# FlyballETS-Board.net
KiCad netlist of a schematic drawn in EAGLE
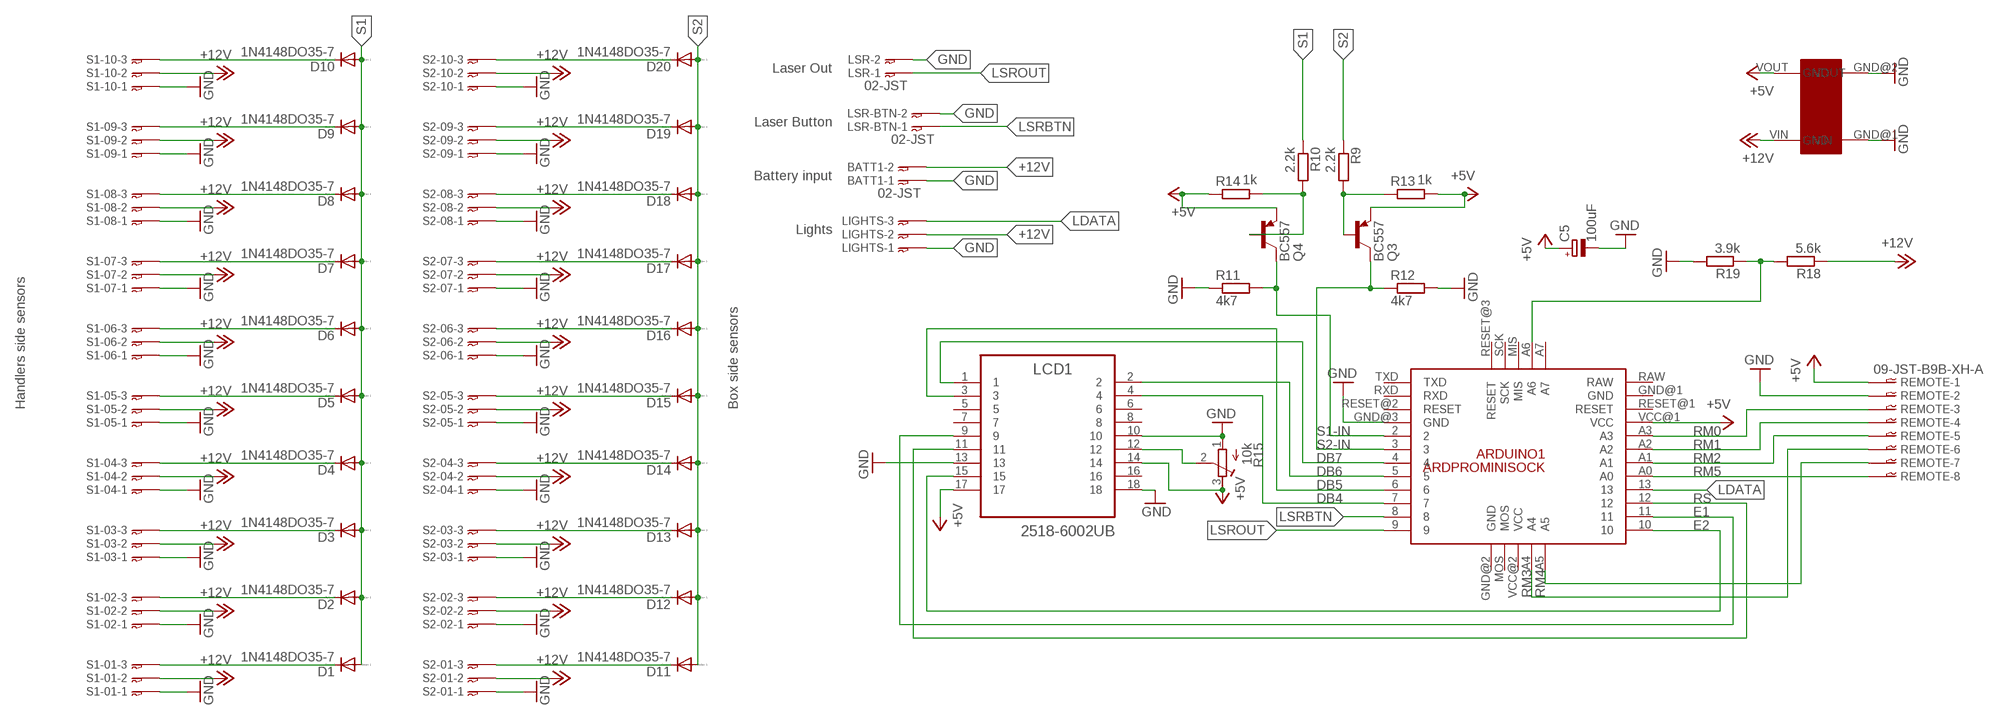
[diagram p0: schematic, sheet 1]

(export (version "E")
  (design (tool "Eeschema 10.0.6"))
  (components
    (comp (ref "ARDUINO1")
      (value "ARDPROMINISOCK")
      (footprint "eagle-import:ARDPROMINISOCK")
      (libsource (lib "eagle-import") (part "ARDPROMINISOCK"))
    )
    (comp (ref "BATT1")
      (value "02-JST")
      (footprint "eagle-import:B2B-XH")
      (libsource (lib "eagle-import") (part "02-JST"))
    )
    (comp (ref "C5")
      (value "100uF")
      (footprint "eagle-import:E2,5-6E")
      (libsource (lib "eagle-import") (part "CPOL-EUE2,5-6E"))
    )
    (comp (ref "D1")
      (value "1N4148DO35-7")
      (footprint "eagle-import:DO35-7")
      (libsource (lib "eagle-import") (part "1N4148DO35-7"))
    )
    (comp (ref "D2")
      (value "1N4148DO35-7")
      (footprint "eagle-import:DO35-7")
      (libsource (lib "eagle-import") (part "1N4148DO35-7"))
    )
    (comp (ref "D3")
      (value "1N4148DO35-7")
      (footprint "eagle-import:DO35-7")
      (libsource (lib "eagle-import") (part "1N4148DO35-7"))
    )
    (comp (ref "D4")
      (value "1N4148DO35-7")
      (footprint "eagle-import:DO35-7")
      (libsource (lib "eagle-import") (part "1N4148DO35-7"))
    )
    (comp (ref "D5")
      (value "1N4148DO35-7")
      (footprint "eagle-import:DO35-7")
      (libsource (lib "eagle-import") (part "1N4148DO35-7"))
    )
    (comp (ref "D6")
      (value "1N4148DO35-7")
      (footprint "eagle-import:DO35-7")
      (libsource (lib "eagle-import") (part "1N4148DO35-7"))
    )
    (comp (ref "D7")
      (value "1N4148DO35-7")
      (footprint "eagle-import:DO35-7")
      (libsource (lib "eagle-import") (part "1N4148DO35-7"))
    )
    (comp (ref "D8")
      (value "1N4148DO35-7")
      (footprint "eagle-import:DO35-7")
      (libsource (lib "eagle-import") (part "1N4148DO35-7"))
    )
    (comp (ref "D9")
      (value "1N4148DO35-7")
      (footprint "eagle-import:DO35-7")
      (libsource (lib "eagle-import") (part "1N4148DO35-7"))
    )
    (comp (ref "D10")
      (value "1N4148DO35-7")
      (footprint "eagle-import:DO35-7")
      (libsource (lib "eagle-import") (part "1N4148DO35-7"))
    )
    (comp (ref "D11")
      (value "1N4148DO35-7")
      (footprint "eagle-import:DO35-7")
      (libsource (lib "eagle-import") (part "1N4148DO35-7"))
    )
    (comp (ref "D12")
      (value "1N4148DO35-7")
      (footprint "eagle-import:DO35-7")
      (libsource (lib "eagle-import") (part "1N4148DO35-7"))
    )
    (comp (ref "D13")
      (value "1N4148DO35-7")
      (footprint "eagle-import:DO35-7")
      (libsource (lib "eagle-import") (part "1N4148DO35-7"))
    )
    (comp (ref "D14")
      (value "1N4148DO35-7")
      (footprint "eagle-import:DO35-7")
      (libsource (lib "eagle-import") (part "1N4148DO35-7"))
    )
    (comp (ref "D15")
      (value "1N4148DO35-7")
      (footprint "eagle-import:DO35-7")
      (libsource (lib "eagle-import") (part "1N4148DO35-7"))
    )
    (comp (ref "D16")
      (value "1N4148DO35-7")
      (footprint "eagle-import:DO35-7")
      (libsource (lib "eagle-import") (part "1N4148DO35-7"))
    )
    (comp (ref "D17")
      (value "1N4148DO35-7")
      (footprint "eagle-import:DO35-7")
      (libsource (lib "eagle-import") (part "1N4148DO35-7"))
    )
    (comp (ref "D18")
      (value "1N4148DO35-7")
      (footprint "eagle-import:DO35-7")
      (libsource (lib "eagle-import") (part "1N4148DO35-7"))
    )
    (comp (ref "D19")
      (value "1N4148DO35-7")
      (footprint "eagle-import:DO35-7")
      (libsource (lib "eagle-import") (part "1N4148DO35-7"))
    )
    (comp (ref "D20")
      (value "1N4148DO35-7")
      (footprint "eagle-import:DO35-7")
      (libsource (lib "eagle-import") (part "1N4148DO35-7"))
    )
    (comp (ref "LCD1")
      (value "2518-6002UB")
      (footprint "eagle-import:3M_2518-6002UB")
      (libsource (lib "eagle-import") (part "2518-6002UB"))
    )
    (comp (ref "LIGHTS")
      (value "03-JST-B3B-XH-A")
      (footprint "eagle-import:B3B-XH")
      (libsource (lib "eagle-import") (part "03-JST-B3B-XH-A"))
    )
    (comp (ref "LSR")
      (value "02-JST")
      (footprint "eagle-import:B2B-XH")
      (libsource (lib "eagle-import") (part "02-JST"))
    )
    (comp (ref "LSR-BTN")
      (value "02-JST")
      (footprint "eagle-import:B2B-XH")
      (libsource (lib "eagle-import") (part "02-JST"))
    )
    (comp (ref "Q3")
      (value "BC557")
      (footprint "eagle-import:TO92")
      (libsource (lib "eagle-import") (part "BC557"))
    )
    (comp (ref "Q4")
      (value "BC557")
      (footprint "eagle-import:TO92")
      (libsource (lib "eagle-import") (part "BC557"))
    )
    (comp (ref "R9")
      (value "2.2k")
      (footprint "eagle-import:0207_10")
      (libsource (lib "eagle-import") (part "R-EU_0207/10"))
    )
    (comp (ref "R10")
      (value "2.2k")
      (footprint "eagle-import:0207_10")
      (libsource (lib "eagle-import") (part "R-EU_0207/10"))
    )
    (comp (ref "R11")
      (value "4k7")
      (footprint "eagle-import:0207_10")
      (libsource (lib "eagle-import") (part "R-EU_0207/10"))
    )
    (comp (ref "R12")
      (value "4k7")
      (footprint "eagle-import:0207_10")
      (libsource (lib "eagle-import") (part "R-EU_0207/10"))
    )
    (comp (ref "R13")
      (value "1k")
      (footprint "eagle-import:0207_10")
      (libsource (lib "eagle-import") (part "R-EU_0207/10"))
    )
    (comp (ref "R14")
      (value "1k")
      (footprint "eagle-import:0207_10")
      (libsource (lib "eagle-import") (part "R-EU_0207/10"))
    )
    (comp (ref "R15")
      (value "10k")
      (footprint "eagle-import:RTRIM3339P")
      (libsource (lib "eagle-import") (part "R-TRIMM3339P"))
    )
    (comp (ref "R18")
      (value "5.6k")
      (footprint "eagle-import:0207_10")
      (libsource (lib "eagle-import") (part "resistor_348_R-EU_0207/10"))
    )
    (comp (ref "R19")
      (value "3.9k")
      (footprint "eagle-import:0207_10")
      (libsource (lib "eagle-import") (part "resistor_348_R-EU_0207/10"))
    )
    (comp (ref "REMOTE")
      (value "09-JST-B9B-XH-A")
      (footprint "eagle-import:B9B-XH")
      (libsource (lib "eagle-import") (part "09-JST-B9B-XH-A"))
    )
    (comp (ref "S1-01")
      (value "03-JST-B3B-XH-A")
      (footprint "eagle-import:B3B-XH")
      (libsource (lib "eagle-import") (part "03-JST-B3B-XH-A"))
    )
    (comp (ref "S1-02")
      (value "03-JST-B3B-XH-A")
      (footprint "eagle-import:B3B-XH")
      (libsource (lib "eagle-import") (part "03-JST-B3B-XH-A"))
    )
    (comp (ref "S1-03")
      (value "03-JST-B3B-XH-A")
      (footprint "eagle-import:B3B-XH")
      (libsource (lib "eagle-import") (part "03-JST-B3B-XH-A"))
    )
    (comp (ref "S1-04")
      (value "03-JST-B3B-XH-A")
      (footprint "eagle-import:B3B-XH")
      (libsource (lib "eagle-import") (part "03-JST-B3B-XH-A"))
    )
    (comp (ref "S1-05")
      (value "03-JST-B3B-XH-A")
      (footprint "eagle-import:B3B-XH")
      (libsource (lib "eagle-import") (part "03-JST-B3B-XH-A"))
    )
    (comp (ref "S1-06")
      (value "03-JST-B3B-XH-A")
      (footprint "eagle-import:B3B-XH")
      (libsource (lib "eagle-import") (part "03-JST-B3B-XH-A"))
    )
    (comp (ref "S1-07")
      (value "03-JST-B3B-XH-A")
      (footprint "eagle-import:B3B-XH")
      (libsource (lib "eagle-import") (part "03-JST-B3B-XH-A"))
    )
    (comp (ref "S1-08")
      (value "03-JST-B3B-XH-A")
      (footprint "eagle-import:B3B-XH")
      (libsource (lib "eagle-import") (part "03-JST-B3B-XH-A"))
    )
    (comp (ref "S1-09")
      (value "03-JST-B3B-XH-A")
      (footprint "eagle-import:B3B-XH")
      (libsource (lib "eagle-import") (part "03-JST-B3B-XH-A"))
    )
    (comp (ref "S1-10")
      (value "03-JST-B3B-XH-A")
      (footprint "eagle-import:B3B-XH")
      (libsource (lib "eagle-import") (part "03-JST-B3B-XH-A"))
    )
    (comp (ref "S2-01")
      (value "03-JST-B3B-XH-A")
      (footprint "eagle-import:B3B-XH")
      (libsource (lib "eagle-import") (part "03-JST-B3B-XH-A"))
    )
    (comp (ref "S2-02")
      (value "03-JST-B3B-XH-A")
      (footprint "eagle-import:B3B-XH")
      (libsource (lib "eagle-import") (part "03-JST-B3B-XH-A"))
    )
    (comp (ref "S2-03")
      (value "03-JST-B3B-XH-A")
      (footprint "eagle-import:B3B-XH")
      (libsource (lib "eagle-import") (part "03-JST-B3B-XH-A"))
    )
    (comp (ref "S2-04")
      (value "03-JST-B3B-XH-A")
      (footprint "eagle-import:B3B-XH")
      (libsource (lib "eagle-import") (part "03-JST-B3B-XH-A"))
    )
    (comp (ref "S2-05")
      (value "03-JST-B3B-XH-A")
      (footprint "eagle-import:B3B-XH")
      (libsource (lib "eagle-import") (part "03-JST-B3B-XH-A"))
    )
    (comp (ref "S2-06")
      (value "03-JST-B3B-XH-A")
      (footprint "eagle-import:B3B-XH")
      (libsource (lib "eagle-import") (part "03-JST-B3B-XH-A"))
    )
    (comp (ref "S2-07")
      (value "03-JST-B3B-XH-A")
      (footprint "eagle-import:B3B-XH")
      (libsource (lib "eagle-import") (part "03-JST-B3B-XH-A"))
    )
    (comp (ref "S2-08")
      (value "03-JST-B3B-XH-A")
      (footprint "eagle-import:B3B-XH")
      (libsource (lib "eagle-import") (part "03-JST-B3B-XH-A"))
    )
    (comp (ref "S2-09")
      (value "03-JST-B3B-XH-A")
      (footprint "eagle-import:B3B-XH")
      (libsource (lib "eagle-import") (part "03-JST-B3B-XH-A"))
    )
    (comp (ref "S2-10")
      (value "03-JST-B3B-XH-A")
      (footprint "eagle-import:B3B-XH")
      (libsource (lib "eagle-import") (part "03-JST-B3B-XH-A"))
    )
    (comp (ref "U$2")
      (value "LM2596-BOARD")
      (footprint "eagle-import:LM2596-BOARD")
      (libsource (lib "eagle-import") (part "LM2596-BOARD"))
    )
  )
  (nets
    (net (code "1") (name "+5V") (class "Default")
      (node (ref "ARDUINO1") (pin "VCC@1") (pinfunction "VCC_VCC@1") (pintype "bidirectional"))
      (node (ref "C5") (pin "+") (pinfunction "+_+") (pintype "passive"))
      (node (ref "LCD1") (pin "14") (pinfunction "14_14") (pintype "passive"))
      (node (ref "LCD1") (pin "17") (pinfunction "17_17") (pintype "passive"))
      (node (ref "Q3") (pin "1") (pinfunction "E_1") (pintype "passive"))
      (node (ref "Q4") (pin "1") (pinfunction "E_1") (pintype "passive"))
      (node (ref "R13") (pin "2") (pinfunction "2_2") (pintype "passive"))
      (node (ref "R14") (pin "1") (pinfunction "1_1") (pintype "passive"))
      (node (ref "R15") (pin "3") (pinfunction "E_3") (pintype "passive"))
      (node (ref "REMOTE") (pin "P$1") (pinfunction "1_P$1") (pintype "passive"))
      (node (ref "U$2") (pin "VOUT") (pinfunction "VOUT_VOUT") (pintype "bidirectional"))
    )
    (net (code "2") (name "+12V") (class "Default")
      (node (ref "BATT1") (pin "P$2") (pinfunction "1_P$2") (pintype "passive"))
      (node (ref "LIGHTS") (pin "P$2") (pinfunction "1_P$2") (pintype "passive"))
      (node (ref "R18") (pin "1") (pinfunction "1_1") (pintype "passive"))
      (node (ref "S1-01") (pin "P$2") (pinfunction "1_P$2") (pintype "passive"))
      (node (ref "S1-02") (pin "P$2") (pinfunction "1_P$2") (pintype "passive"))
      (node (ref "S1-03") (pin "P$2") (pinfunction "1_P$2") (pintype "passive"))
      (node (ref "S1-04") (pin "P$2") (pinfunction "1_P$2") (pintype "passive"))
      (node (ref "S1-05") (pin "P$2") (pinfunction "1_P$2") (pintype "passive"))
      (node (ref "S1-06") (pin "P$2") (pinfunction "1_P$2") (pintype "passive"))
      (node (ref "S1-07") (pin "P$2") (pinfunction "1_P$2") (pintype "passive"))
      (node (ref "S1-08") (pin "P$2") (pinfunction "1_P$2") (pintype "passive"))
      (node (ref "S1-09") (pin "P$2") (pinfunction "1_P$2") (pintype "passive"))
      (node (ref "S1-10") (pin "P$2") (pinfunction "1_P$2") (pintype "passive"))
      (node (ref "S2-01") (pin "P$2") (pinfunction "1_P$2") (pintype "passive"))
      (node (ref "S2-02") (pin "P$2") (pinfunction "1_P$2") (pintype "passive"))
      (node (ref "S2-03") (pin "P$2") (pinfunction "1_P$2") (pintype "passive"))
      (node (ref "S2-04") (pin "P$2") (pinfunction "1_P$2") (pintype "passive"))
      (node (ref "S2-05") (pin "P$2") (pinfunction "1_P$2") (pintype "passive"))
      (node (ref "S2-06") (pin "P$2") (pinfunction "1_P$2") (pintype "passive"))
      (node (ref "S2-07") (pin "P$2") (pinfunction "1_P$2") (pintype "passive"))
      (node (ref "S2-08") (pin "P$2") (pinfunction "1_P$2") (pintype "passive"))
      (node (ref "S2-09") (pin "P$2") (pinfunction "1_P$2") (pintype "passive"))
      (node (ref "S2-10") (pin "P$2") (pinfunction "1_P$2") (pintype "passive"))
      (node (ref "U$2") (pin "VIN") (pinfunction "VIN_VIN") (pintype "bidirectional"))
    )
    (net (code "3") (name "/DB4") (class "Default")
      (node (ref "ARDUINO1") (pin "7") (pinfunction "7_7") (pintype "bidirectional"))
      (node (ref "LCD1") (pin "4") (pinfunction "4_4") (pintype "passive"))
    )
    (net (code "4") (name "/DB5") (class "Default")
      (node (ref "ARDUINO1") (pin "6") (pinfunction "6_6") (pintype "bidirectional"))
      (node (ref "LCD1") (pin "3") (pinfunction "3_3") (pintype "passive"))
    )
    (net (code "5") (name "/DB6") (class "Default")
      (node (ref "ARDUINO1") (pin "5") (pinfunction "5_5") (pintype "bidirectional"))
      (node (ref "LCD1") (pin "2") (pinfunction "2_2") (pintype "passive"))
    )
    (net (code "6") (name "/DB7") (class "Default")
      (node (ref "ARDUINO1") (pin "4") (pinfunction "4_4") (pintype "bidirectional"))
      (node (ref "LCD1") (pin "1") (pinfunction "1_1") (pintype "passive"))
    )
    (net (code "7") (name "/E1") (class "Default")
      (node (ref "ARDUINO1") (pin "11") (pinfunction "11_11") (pintype "bidirectional"))
      (node (ref "LCD1") (pin "9") (pinfunction "9_9") (pintype "passive"))
    )
    (net (code "8") (name "/E2") (class "Default")
      (node (ref "ARDUINO1") (pin "10") (pinfunction "10_10") (pintype "bidirectional"))
      (node (ref "LCD1") (pin "15") (pinfunction "15_15") (pintype "passive"))
    )
    (net (code "9") (name "/RM0") (class "Default")
      (node (ref "ARDUINO1") (pin "A3") (pinfunction "A3_A3") (pintype "bidirectional"))
      (node (ref "REMOTE") (pin "P$3") (pinfunction "1_P$3") (pintype "passive"))
    )
    (net (code "10") (name "/RM1") (class "Default")
      (node (ref "ARDUINO1") (pin "A2") (pinfunction "A2_A2") (pintype "bidirectional"))
      (node (ref "REMOTE") (pin "P$4") (pinfunction "1_P$4") (pintype "passive"))
    )
    (net (code "11") (name "/RM2") (class "Default")
      (node (ref "ARDUINO1") (pin "A1") (pinfunction "A1_A1") (pintype "bidirectional"))
      (node (ref "REMOTE") (pin "P$5") (pinfunction "1_P$5") (pintype "passive"))
    )
    (net (code "12") (name "/RM3") (class "Default")
      (node (ref "ARDUINO1") (pin "A4") (pinfunction "A4_A4") (pintype "bidirectional"))
      (node (ref "REMOTE") (pin "P$6") (pinfunction "1_P$6") (pintype "passive"))
    )
    (net (code "13") (name "/RM4") (class "Default")
      (node (ref "ARDUINO1") (pin "A5") (pinfunction "A5_A5") (pintype "bidirectional"))
      (node (ref "REMOTE") (pin "P$7") (pinfunction "1_P$7") (pintype "passive"))
    )
    (net (code "14") (name "/RM5") (class "Default")
      (node (ref "ARDUINO1") (pin "A0") (pinfunction "A0_A0") (pintype "bidirectional"))
      (node (ref "REMOTE") (pin "P$8") (pinfunction "1_P$8") (pintype "passive"))
    )
    (net (code "15") (name "/RS") (class "Default")
      (node (ref "ARDUINO1") (pin "12") (pinfunction "12_12") (pintype "bidirectional"))
      (node (ref "LCD1") (pin "11") (pinfunction "11_11") (pintype "passive"))
    )
    (net (code "16") (name "/S1-IN") (class "Default")
      (node (ref "ARDUINO1") (pin "2") (pinfunction "2_2") (pintype "bidirectional"))
      (node (ref "Q4") (pin "3") (pinfunction "C_3") (pintype "passive"))
      (node (ref "R11") (pin "2") (pinfunction "2_2") (pintype "passive"))
    )
    (net (code "17") (name "/S2-IN") (class "Default")
      (node (ref "ARDUINO1") (pin "3") (pinfunction "3_3") (pintype "bidirectional"))
      (node (ref "Q3") (pin "3") (pinfunction "C_3") (pintype "passive"))
      (node (ref "R12") (pin "1") (pinfunction "1_1") (pintype "passive"))
    )
    (net (code "18") (name "GND") (class "Default")
      (node (ref "ARDUINO1") (pin "GND@3") (pinfunction "GND_GND@3") (pintype "bidirectional"))
      (node (ref "BATT1") (pin "P$1") (pinfunction "1_P$1") (pintype "passive"))
      (node (ref "C5") (pin "-") (pinfunction "-_-") (pintype "passive"))
      (node (ref "LCD1") (pin "10") (pinfunction "10_10") (pintype "passive"))
      (node (ref "LCD1") (pin "13") (pinfunction "13_13") (pintype "passive"))
      (node (ref "LCD1") (pin "18") (pinfunction "18_18") (pintype "passive"))
      (node (ref "LIGHTS") (pin "P$1") (pinfunction "1_P$1") (pintype "passive"))
      (node (ref "LSR") (pin "P$2") (pinfunction "1_P$2") (pintype "passive"))
      (node (ref "LSR-BTN") (pin "P$2") (pinfunction "1_P$2") (pintype "passive"))
      (node (ref "R11") (pin "1") (pinfunction "1_1") (pintype "passive"))
      (node (ref "R12") (pin "2") (pinfunction "2_2") (pintype "passive"))
      (node (ref "R15") (pin "1") (pinfunction "A_1") (pintype "passive"))
      (node (ref "R19") (pin "2") (pinfunction "2_2") (pintype "passive"))
      (node (ref "REMOTE") (pin "P$2") (pinfunction "1_P$2") (pintype "passive"))
      (node (ref "S1-01") (pin "P$1") (pinfunction "1_P$1") (pintype "passive"))
      (node (ref "S1-02") (pin "P$1") (pinfunction "1_P$1") (pintype "passive"))
      (node (ref "S1-03") (pin "P$1") (pinfunction "1_P$1") (pintype "passive"))
      (node (ref "S1-04") (pin "P$1") (pinfunction "1_P$1") (pintype "passive"))
      (node (ref "S1-05") (pin "P$1") (pinfunction "1_P$1") (pintype "passive"))
      (node (ref "S1-06") (pin "P$1") (pinfunction "1_P$1") (pintype "passive"))
      (node (ref "S1-07") (pin "P$1") (pinfunction "1_P$1") (pintype "passive"))
      (node (ref "S1-08") (pin "P$1") (pinfunction "1_P$1") (pintype "passive"))
      (node (ref "S1-09") (pin "P$1") (pinfunction "1_P$1") (pintype "passive"))
      (node (ref "S1-10") (pin "P$1") (pinfunction "1_P$1") (pintype "passive"))
      (node (ref "S2-01") (pin "P$1") (pinfunction "1_P$1") (pintype "passive"))
      (node (ref "S2-02") (pin "P$1") (pinfunction "1_P$1") (pintype "passive"))
      (node (ref "S2-03") (pin "P$1") (pinfunction "1_P$1") (pintype "passive"))
      (node (ref "S2-04") (pin "P$1") (pinfunction "1_P$1") (pintype "passive"))
      (node (ref "S2-05") (pin "P$1") (pinfunction "1_P$1") (pintype "passive"))
      (node (ref "S2-06") (pin "P$1") (pinfunction "1_P$1") (pintype "passive"))
      (node (ref "S2-07") (pin "P$1") (pinfunction "1_P$1") (pintype "passive"))
      (node (ref "S2-08") (pin "P$1") (pinfunction "1_P$1") (pintype "passive"))
      (node (ref "S2-09") (pin "P$1") (pinfunction "1_P$1") (pintype "passive"))
      (node (ref "S2-10") (pin "P$1") (pinfunction "1_P$1") (pintype "passive"))
      (node (ref "U$2") (pin "GND@1") (pinfunction "GND_GND@1") (pintype "bidirectional"))
      (node (ref "U$2") (pin "GND@2") (pinfunction "GND_GND@2") (pintype "bidirectional"))
    )
    (net (code "19") (name "LDATA") (class "Default")
      (node (ref "ARDUINO1") (pin "13") (pinfunction "13_13") (pintype "bidirectional"))
      (node (ref "LIGHTS") (pin "P$3") (pinfunction "1_P$3") (pintype "passive"))
    )
    (net (code "20") (name "LSRBTN") (class "Default")
      (node (ref "ARDUINO1") (pin "8") (pinfunction "8_8") (pintype "bidirectional"))
      (node (ref "LSR-BTN") (pin "P$1") (pinfunction "1_P$1") (pintype "passive"))
    )
    (net (code "21") (name "LSROUT") (class "Default")
      (node (ref "ARDUINO1") (pin "9") (pinfunction "9_9") (pintype "bidirectional"))
      (node (ref "LSR") (pin "P$1") (pinfunction "1_P$1") (pintype "passive"))
    )
    (net (code "22") (name "Net-(ARDUINO1-PadA6)") (class "Default")
      (node (ref "ARDUINO1") (pin "A6") (pinfunction "A6_A6") (pintype "bidirectional"))
      (node (ref "R18") (pin "2") (pinfunction "2_2") (pintype "passive"))
      (node (ref "R19") (pin "1") (pinfunction "1_1") (pintype "passive"))
    )
    (net (code "23") (name "Net-(Q3-B)") (class "Default")
      (node (ref "Q3") (pin "2") (pinfunction "B_2") (pintype "passive"))
      (node (ref "R13") (pin "1") (pinfunction "1_1") (pintype "passive"))
      (node (ref "R9") (pin "2") (pinfunction "2_2") (pintype "passive"))
    )
    (net (code "24") (name "Net-(Q4-B)") (class "Default")
      (node (ref "Q4") (pin "2") (pinfunction "B_2") (pintype "passive"))
      (node (ref "R10") (pin "2") (pinfunction "2_2") (pintype "passive"))
      (node (ref "R14") (pin "2") (pinfunction "2_2") (pintype "passive"))
    )
    (net (code "25") (name "Net-(R15-S)") (class "Default")
      (node (ref "LCD1") (pin "12") (pinfunction "12_12") (pintype "passive"))
      (node (ref "R15") (pin "2") (pinfunction "S_2") (pintype "passive"))
    )
    (net (code "26") (name "Net-(S1-01C-1)") (class "Default")
      (node (ref "D1") (pin "C") (pinfunction "C_C") (pintype "passive"))
      (node (ref "S1-01") (pin "P$3") (pinfunction "1_P$3") (pintype "passive"))
    )
    (net (code "27") (name "Net-(S1-02C-1)") (class "Default")
      (node (ref "D2") (pin "C") (pinfunction "C_C") (pintype "passive"))
      (node (ref "S1-02") (pin "P$3") (pinfunction "1_P$3") (pintype "passive"))
    )
    (net (code "28") (name "Net-(S1-03C-1)") (class "Default")
      (node (ref "D3") (pin "C") (pinfunction "C_C") (pintype "passive"))
      (node (ref "S1-03") (pin "P$3") (pinfunction "1_P$3") (pintype "passive"))
    )
    (net (code "29") (name "Net-(S1-04C-1)") (class "Default")
      (node (ref "D4") (pin "C") (pinfunction "C_C") (pintype "passive"))
      (node (ref "S1-04") (pin "P$3") (pinfunction "1_P$3") (pintype "passive"))
    )
    (net (code "30") (name "Net-(S1-05C-1)") (class "Default")
      (node (ref "D5") (pin "C") (pinfunction "C_C") (pintype "passive"))
      (node (ref "S1-05") (pin "P$3") (pinfunction "1_P$3") (pintype "passive"))
    )
    (net (code "31") (name "Net-(S1-06C-1)") (class "Default")
      (node (ref "D6") (pin "C") (pinfunction "C_C") (pintype "passive"))
      (node (ref "S1-06") (pin "P$3") (pinfunction "1_P$3") (pintype "passive"))
    )
    (net (code "32") (name "Net-(S1-07C-1)") (class "Default")
      (node (ref "D7") (pin "C") (pinfunction "C_C") (pintype "passive"))
      (node (ref "S1-07") (pin "P$3") (pinfunction "1_P$3") (pintype "passive"))
    )
    (net (code "33") (name "Net-(S1-08C-1)") (class "Default")
      (node (ref "D8") (pin "C") (pinfunction "C_C") (pintype "passive"))
      (node (ref "S1-08") (pin "P$3") (pinfunction "1_P$3") (pintype "passive"))
    )
    (net (code "34") (name "Net-(S1-09C-1)") (class "Default")
      (node (ref "D9") (pin "C") (pinfunction "C_C") (pintype "passive"))
      (node (ref "S1-09") (pin "P$3") (pinfunction "1_P$3") (pintype "passive"))
    )
    (net (code "35") (name "Net-(S1-10C-1)") (class "Default")
      (node (ref "D10") (pin "C") (pinfunction "C_C") (pintype "passive"))
      (node (ref "S1-10") (pin "P$3") (pinfunction "1_P$3") (pintype "passive"))
    )
    (net (code "36") (name "Net-(S2-01C-1)") (class "Default")
      (node (ref "D11") (pin "C") (pinfunction "C_C") (pintype "passive"))
      (node (ref "S2-01") (pin "P$3") (pinfunction "1_P$3") (pintype "passive"))
    )
    (net (code "37") (name "Net-(S2-02C-1)") (class "Default")
      (node (ref "D12") (pin "C") (pinfunction "C_C") (pintype "passive"))
      (node (ref "S2-02") (pin "P$3") (pinfunction "1_P$3") (pintype "passive"))
    )
    (net (code "38") (name "Net-(S2-03C-1)") (class "Default")
      (node (ref "D13") (pin "C") (pinfunction "C_C") (pintype "passive"))
      (node (ref "S2-03") (pin "P$3") (pinfunction "1_P$3") (pintype "passive"))
    )
    (net (code "39") (name "Net-(S2-04C-1)") (class "Default")
      (node (ref "D14") (pin "C") (pinfunction "C_C") (pintype "passive"))
      (node (ref "S2-04") (pin "P$3") (pinfunction "1_P$3") (pintype "passive"))
    )
    (net (code "40") (name "Net-(S2-05C-1)") (class "Default")
      (node (ref "D15") (pin "C") (pinfunction "C_C") (pintype "passive"))
      (node (ref "S2-05") (pin "P$3") (pinfunction "1_P$3") (pintype "passive"))
    )
    (net (code "41") (name "Net-(S2-06C-1)") (class "Default")
      (node (ref "D16") (pin "C") (pinfunction "C_C") (pintype "passive"))
      (node (ref "S2-06") (pin "P$3") (pinfunction "1_P$3") (pintype "passive"))
    )
    (net (code "42") (name "Net-(S2-07C-1)") (class "Default")
      (node (ref "D17") (pin "C") (pinfunction "C_C") (pintype "passive"))
      (node (ref "S2-07") (pin "P$3") (pinfunction "1_P$3") (pintype "passive"))
    )
    (net (code "43") (name "Net-(S2-08C-1)") (class "Default")
      (node (ref "D18") (pin "C") (pinfunction "C_C") (pintype "passive"))
      (node (ref "S2-08") (pin "P$3") (pinfunction "1_P$3") (pintype "passive"))
    )
    (net (code "44") (name "Net-(S2-09C-1)") (class "Default")
      (node (ref "D19") (pin "C") (pinfunction "C_C") (pintype "passive"))
      (node (ref "S2-09") (pin "P$3") (pinfunction "1_P$3") (pintype "passive"))
    )
    (net (code "45") (name "Net-(S2-10C-1)") (class "Default")
      (node (ref "D20") (pin "C") (pinfunction "C_C") (pintype "passive"))
      (node (ref "S2-10") (pin "P$3") (pinfunction "1_P$3") (pintype "passive"))
    )
    (net (code "46") (name "S1") (class "Default")
      (node (ref "D1") (pin "A") (pinfunction "A_A") (pintype "passive"))
      (node (ref "D10") (pin "A") (pinfunction "A_A") (pintype "passive"))
      (node (ref "D2") (pin "A") (pinfunction "A_A") (pintype "passive"))
      (node (ref "D3") (pin "A") (pinfunction "A_A") (pintype "passive"))
      (node (ref "D4") (pin "A") (pinfunction "A_A") (pintype "passive"))
      (node (ref "D5") (pin "A") (pinfunction "A_A") (pintype "passive"))
      (node (ref "D6") (pin "A") (pinfunction "A_A") (pintype "passive"))
      (node (ref "D7") (pin "A") (pinfunction "A_A") (pintype "passive"))
      (node (ref "D8") (pin "A") (pinfunction "A_A") (pintype "passive"))
      (node (ref "D9") (pin "A") (pinfunction "A_A") (pintype "passive"))
      (node (ref "R10") (pin "1") (pinfunction "1_1") (pintype "passive"))
    )
    (net (code "47") (name "S2") (class "Default")
      (node (ref "D11") (pin "A") (pinfunction "A_A") (pintype "passive"))
      (node (ref "D12") (pin "A") (pinfunction "A_A") (pintype "passive"))
      (node (ref "D13") (pin "A") (pinfunction "A_A") (pintype "passive"))
      (node (ref "D14") (pin "A") (pinfunction "A_A") (pintype "passive"))
      (node (ref "D15") (pin "A") (pinfunction "A_A") (pintype "passive"))
      (node (ref "D16") (pin "A") (pinfunction "A_A") (pintype "passive"))
      (node (ref "D17") (pin "A") (pinfunction "A_A") (pintype "passive"))
      (node (ref "D18") (pin "A") (pinfunction "A_A") (pintype "passive"))
      (node (ref "D19") (pin "A") (pinfunction "A_A") (pintype "passive"))
      (node (ref "D20") (pin "A") (pinfunction "A_A") (pintype "passive"))
      (node (ref "R9") (pin "1") (pinfunction "1_1") (pintype "passive"))
    )
    (net (code "48") (name "unconnected-(ARDUINO1-GND-PadGND@1)") (class "Default")
      (node (ref "ARDUINO1") (pin "GND@1") (pinfunction "GND_GND@1") (pintype "bidirectional"))
    )
    (net (code "49") (name "unconnected-(ARDUINO1-GND-PadGND@2)") (class "Default")
      (node (ref "ARDUINO1") (pin "GND@2") (pinfunction "GND_GND@2") (pintype "bidirectional"))
    )
    (net (code "50") (name "unconnected-(ARDUINO1-PadA7)") (class "Default")
      (node (ref "ARDUINO1") (pin "A7") (pinfunction "A7_A7") (pintype "bidirectional"))
    )
    (net (code "51") (name "unconnected-(ARDUINO1-PadMIS)") (class "Default")
      (node (ref "ARDUINO1") (pin "MIS") (pinfunction "MIS_MIS") (pintype "bidirectional"))
    )
    (net (code "52") (name "unconnected-(ARDUINO1-PadMOS)") (class "Default")
      (node (ref "ARDUINO1") (pin "MOS") (pinfunction "MOS_MOS") (pintype "bidirectional"))
    )
    (net (code "53") (name "unconnected-(ARDUINO1-PadRAW)") (class "Default")
      (node (ref "ARDUINO1") (pin "RAW") (pinfunction "RAW_RAW") (pintype "bidirectional"))
    )
    (net (code "54") (name "unconnected-(ARDUINO1-PadRXD)") (class "Default")
      (node (ref "ARDUINO1") (pin "RXD") (pinfunction "RXD_RXD") (pintype "bidirectional"))
    )
    (net (code "55") (name "unconnected-(ARDUINO1-PadSCK)") (class "Default")
      (node (ref "ARDUINO1") (pin "SCK") (pinfunction "SCK_SCK") (pintype "bidirectional"))
    )
    (net (code "56") (name "unconnected-(ARDUINO1-PadTXD)") (class "Default")
      (node (ref "ARDUINO1") (pin "TXD") (pinfunction "TXD_TXD") (pintype "bidirectional"))
    )
    (net (code "57") (name "unconnected-(ARDUINO1-RESET-PadRESET@1)") (class "Default")
      (node (ref "ARDUINO1") (pin "RESET@1") (pinfunction "RESET_RESET@1") (pintype "bidirectional"))
    )
    (net (code "58") (name "unconnected-(ARDUINO1-RESET-PadRESET@2)") (class "Default")
      (node (ref "ARDUINO1") (pin "RESET@2") (pinfunction "RESET_RESET@2") (pintype "bidirectional"))
    )
    (net (code "59") (name "unconnected-(ARDUINO1-RESET-PadRESET@3)") (class "Default")
      (node (ref "ARDUINO1") (pin "RESET@3") (pinfunction "RESET_RESET@3") (pintype "bidirectional"))
    )
    (net (code "60") (name "unconnected-(ARDUINO1-VCC-PadVCC@2)") (class "Default")
      (node (ref "ARDUINO1") (pin "VCC@2") (pinfunction "VCC_VCC@2") (pintype "bidirectional"))
    )
    (net (code "61") (name "unconnected-(LCD1-Pad5)") (class "Default")
      (node (ref "LCD1") (pin "5") (pinfunction "5_5") (pintype "passive"))
    )
    (net (code "62") (name "unconnected-(LCD1-Pad6)") (class "Default")
      (node (ref "LCD1") (pin "6") (pinfunction "6_6") (pintype "passive"))
    )
    (net (code "63") (name "unconnected-(LCD1-Pad7)") (class "Default")
      (node (ref "LCD1") (pin "7") (pinfunction "7_7") (pintype "passive"))
    )
    (net (code "64") (name "unconnected-(LCD1-Pad8)") (class "Default")
      (node (ref "LCD1") (pin "8") (pinfunction "8_8") (pintype "passive"))
    )
    (net (code "65") (name "unconnected-(LCD1-Pad16)") (class "Default")
      (node (ref "LCD1") (pin "16") (pinfunction "16_16") (pintype "passive"))
    )
  )
)
